# node.net
KiCad netlist of a schematic drawn in EAGLE
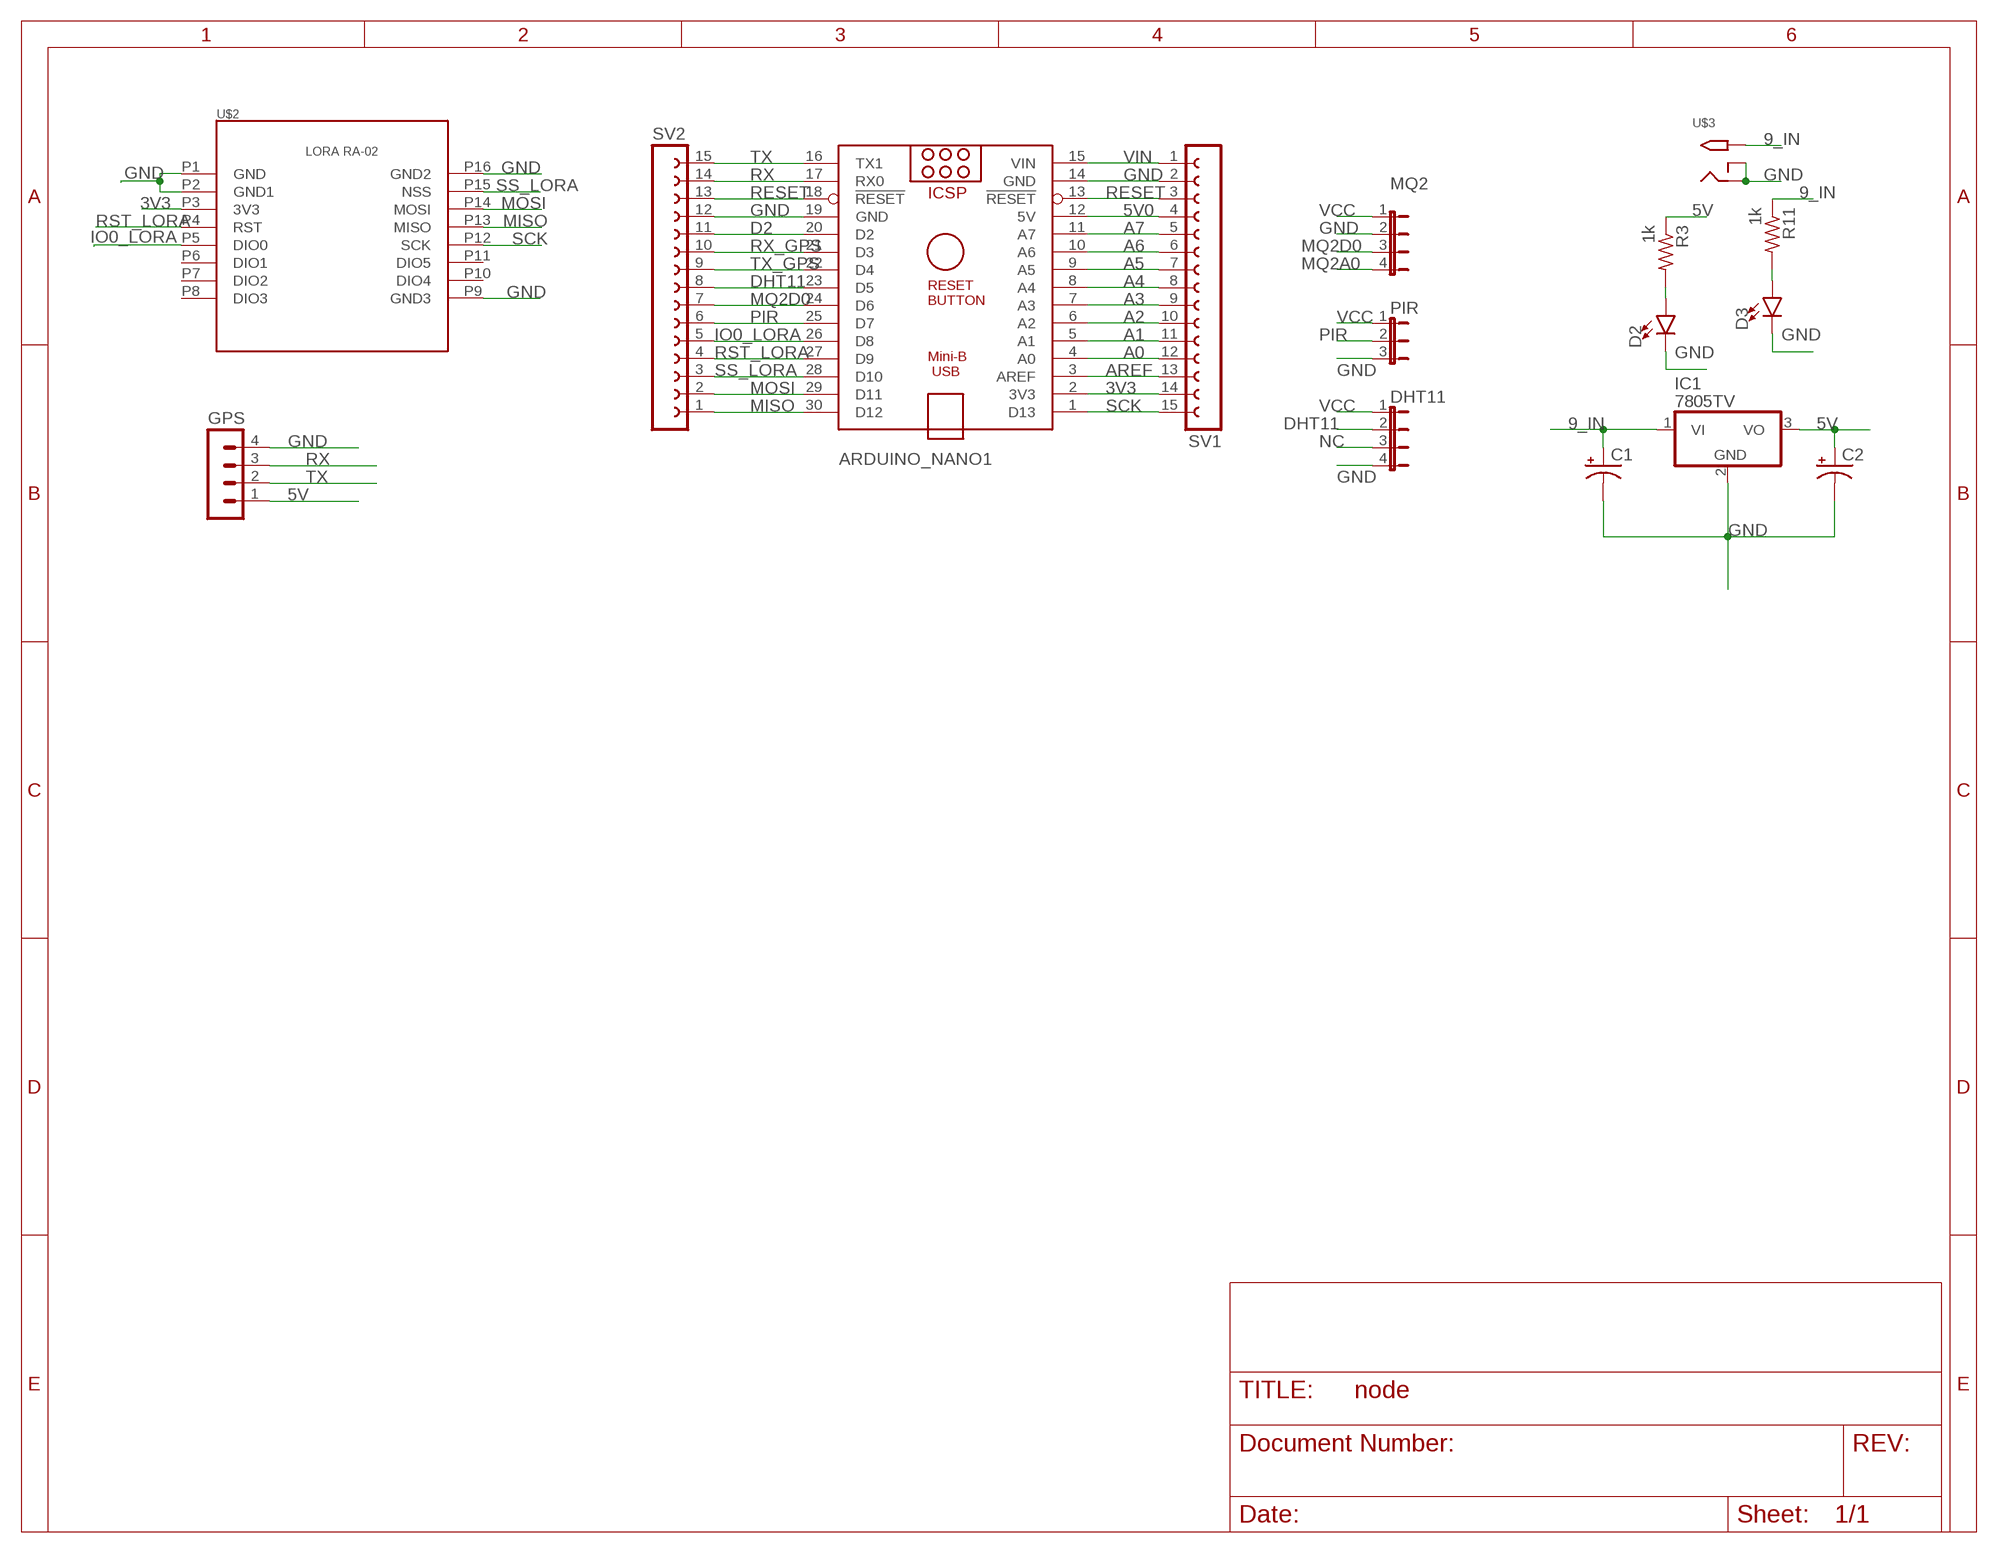
[diagram p0: schematic, sheet 1]

(export (version "E")
  (design (tool "Eeschema 10.0.6"))
  (components
    (comp (ref "ARDUINO_NANO1")
      (value "ARDUINO_NANO")
      (footprint "eagle-import:ARDUINO_NANO")
      (libsource (lib "eagle-import") (part "ARDUINO_NANO"))
    )
    (comp (ref "C1")
      (value "CPOL-USE3.5-8")
      (footprint "eagle-import:E3,5-8")
      (libsource (lib "eagle-import") (part "CPOL-USE3.5-8"))
    )
    (comp (ref "C2")
      (value "CPOL-USE3.5-8")
      (footprint "eagle-import:E3,5-8")
      (libsource (lib "eagle-import") (part "CPOL-USE3.5-8"))
    )
    (comp (ref "D2")
      (value "LED3MM")
      (footprint "eagle-import:LED_3MM")
      (libsource (lib "eagle-import") (part "LED3MM"))
    )
    (comp (ref "D3")
      (value "LED3MM")
      (footprint "eagle-import:LED_3MM")
      (libsource (lib "eagle-import") (part "LED3MM"))
    )
    (comp (ref "DHT11")
      (value "JP4E")
      (footprint "eagle-import:JP4")
      (libsource (lib "eagle-import") (part "JP4E"))
    )
    (comp (ref "GPS")
      (value "MA04-1")
      (footprint "eagle-import:MA04-1")
      (libsource (lib "eagle-import") (part "MA04-1"))
    )
    (comp (ref "IC1")
      (value "7805TV")
      (footprint "eagle-import:TO220V")
      (libsource (lib "eagle-import") (part "78TV05"))
    )
    (comp (ref "MQ2")
      (value "JP4E")
      (footprint "eagle-import:JP4")
      (libsource (lib "eagle-import") (part "JP4E"))
    )
    (comp (ref "PIR")
      (value "JP2E")
      (footprint "eagle-import:JP2")
      (libsource (lib "eagle-import") (part "JP2E"))
    )
    (comp (ref "R3")
      (value "1k")
      (footprint "eagle-import:M0805")
      (libsource (lib "eagle-import") (part "R-US_M0805"))
    )
    (comp (ref "R11")
      (value "1k")
      (footprint "eagle-import:M0805")
      (libsource (lib "eagle-import") (part "R-US_M0805"))
    )
    (comp (ref "SV1")
      (value "FE15-1")
      (footprint "eagle-import:FE15")
      (libsource (lib "eagle-import") (part "FE15-1"))
    )
    (comp (ref "SV2")
      (value "FE15-1")
      (footprint "eagle-import:FE15")
      (libsource (lib "eagle-import") (part "FE15-1"))
    )
    (comp (ref "U$2")
      (value "LORA_RA-02")
      (footprint "eagle-import:RA-02")
      (libsource (lib "eagle-import") (part "LORA_RA-02"))
    )
    (comp (ref "U$3")
      (value "2.1MMJACKTHM")
      (footprint "eagle-import:PJ-102A")
      (libsource (lib "eagle-import") (part "2.1MMJACKTHM"))
    )
  )
  (nets
    (net (code "1") (name "/3V3") (class "Default")
      (node (ref "ARDUINO_NANO1") (pin "2") (pinfunction "3V3_2") (pintype "output"))
      (node (ref "SV1") (pin "14") (pinfunction "14_14") (pintype "passive"))
      (node (ref "U$2") (pin "P3") (pinfunction "3V3_P3") (pintype "bidirectional"))
    )
    (net (code "2") (name "/5V") (class "Default")
      (node (ref "C2") (pin "+") (pinfunction "+_+") (pintype "passive"))
      (node (ref "GPS") (pin "1") (pinfunction "1_1") (pintype "passive"))
      (node (ref "IC1") (pin "3") (pinfunction "VO_3") (pintype "passive"))
      (node (ref "R3") (pin "1") (pinfunction "1_1") (pintype "passive"))
    )
    (net (code "3") (name "/5V0") (class "Default")
      (node (ref "ARDUINO_NANO1") (pin "12") (pinfunction "5V_12") (pintype "power_in"))
      (node (ref "SV1") (pin "4") (pinfunction "4_4") (pintype "passive"))
    )
    (net (code "4") (name "/9_IN") (class "Default")
      (node (ref "C1") (pin "+") (pinfunction "+_+") (pintype "passive"))
      (node (ref "IC1") (pin "1") (pinfunction "VI_1") (pintype "input"))
      (node (ref "R11") (pin "1") (pinfunction "1_1") (pintype "passive"))
      (node (ref "U$3") (pin "TIP") (pinfunction "TIP_TIP") (pintype "bidirectional"))
    )
    (net (code "5") (name "/A0") (class "Default")
      (node (ref "ARDUINO_NANO1") (pin "4") (pinfunction "A0_4") (pintype "bidirectional"))
      (node (ref "SV1") (pin "12") (pinfunction "12_12") (pintype "passive"))
    )
    (net (code "6") (name "/A1") (class "Default")
      (node (ref "ARDUINO_NANO1") (pin "5") (pinfunction "A1_5") (pintype "bidirectional"))
      (node (ref "SV1") (pin "11") (pinfunction "11_11") (pintype "passive"))
    )
    (net (code "7") (name "/A2") (class "Default")
      (node (ref "ARDUINO_NANO1") (pin "6") (pinfunction "A2_6") (pintype "bidirectional"))
      (node (ref "SV1") (pin "10") (pinfunction "10_10") (pintype "passive"))
    )
    (net (code "8") (name "/A3") (class "Default")
      (node (ref "ARDUINO_NANO1") (pin "7") (pinfunction "A3_7") (pintype "bidirectional"))
      (node (ref "SV1") (pin "9") (pinfunction "9_9") (pintype "passive"))
    )
    (net (code "9") (name "/A4") (class "Default")
      (node (ref "ARDUINO_NANO1") (pin "8") (pinfunction "A4_8") (pintype "bidirectional"))
      (node (ref "SV1") (pin "8") (pinfunction "8_8") (pintype "passive"))
    )
    (net (code "10") (name "/A5") (class "Default")
      (node (ref "ARDUINO_NANO1") (pin "9") (pinfunction "A5_9") (pintype "bidirectional"))
      (node (ref "SV1") (pin "7") (pinfunction "7_7") (pintype "passive"))
    )
    (net (code "11") (name "/A6") (class "Default")
      (node (ref "ARDUINO_NANO1") (pin "10") (pinfunction "A6_10") (pintype "bidirectional"))
      (node (ref "SV1") (pin "6") (pinfunction "6_6") (pintype "passive"))
    )
    (net (code "12") (name "/A7") (class "Default")
      (node (ref "ARDUINO_NANO1") (pin "11") (pinfunction "A7_11") (pintype "bidirectional"))
      (node (ref "SV1") (pin "5") (pinfunction "5_5") (pintype "passive"))
    )
    (net (code "13") (name "/AREF") (class "Default")
      (node (ref "ARDUINO_NANO1") (pin "3") (pinfunction "AREF_3") (pintype "input"))
      (node (ref "SV1") (pin "13") (pinfunction "13_13") (pintype "passive"))
    )
    (net (code "14") (name "/D2") (class "Default")
      (node (ref "ARDUINO_NANO1") (pin "20") (pinfunction "D2_20") (pintype "bidirectional"))
      (node (ref "SV2") (pin "11") (pinfunction "11_11") (pintype "passive"))
    )
    (net (code "15") (name "/DHT11") (class "Default")
      (node (ref "ARDUINO_NANO1") (pin "23") (pinfunction "D5_23") (pintype "bidirectional"))
      (node (ref "DHT11") (pin "2") (pinfunction "2_2") (pintype "passive"))
      (node (ref "SV2") (pin "8") (pinfunction "8_8") (pintype "passive"))
    )
    (net (code "16") (name "/GND") (class "Default")
      (node (ref "ARDUINO_NANO1") (pin "14") (pinfunction "GND_14") (pintype "power_in"))
      (node (ref "ARDUINO_NANO1") (pin "19") (pinfunction "GND_19") (pintype "power_in"))
      (node (ref "C1") (pin "-") (pinfunction "-_-") (pintype "passive"))
      (node (ref "C2") (pin "-") (pinfunction "-_-") (pintype "passive"))
      (node (ref "D2") (pin "K") (pinfunction "C_K") (pintype "passive"))
      (node (ref "D3") (pin "K") (pinfunction "C_K") (pintype "passive"))
      (node (ref "DHT11") (pin "4") (pinfunction "4_4") (pintype "passive"))
      (node (ref "GPS") (pin "4") (pinfunction "4_4") (pintype "passive"))
      (node (ref "IC1") (pin "2") (pinfunction "GND_2") (pintype "passive"))
      (node (ref "MQ2") (pin "2") (pinfunction "2_2") (pintype "passive"))
      (node (ref "PIR") (pin "3") (pinfunction "3_3") (pintype "passive"))
      (node (ref "SV1") (pin "2") (pinfunction "2_2") (pintype "passive"))
      (node (ref "SV2") (pin "12") (pinfunction "12_12") (pintype "passive"))
      (node (ref "U$2") (pin "P1") (pinfunction "GND_P1") (pintype "bidirectional"))
      (node (ref "U$2") (pin "P16") (pinfunction "GND2_P16") (pintype "bidirectional"))
      (node (ref "U$2") (pin "P2") (pinfunction "GND1_P2") (pintype "bidirectional"))
      (node (ref "U$2") (pin "P9") (pinfunction "GND3_P9") (pintype "bidirectional"))
      (node (ref "U$3") (pin "RING") (pinfunction "RING_RING") (pintype "bidirectional"))
      (node (ref "U$3") (pin "RING_SW") (pinfunction "RING_SW_RING_SW") (pintype "bidirectional"))
    )
    (net (code "17") (name "/IO0_LORA") (class "Default")
      (node (ref "ARDUINO_NANO1") (pin "26") (pinfunction "D8_26") (pintype "bidirectional"))
      (node (ref "SV2") (pin "5") (pinfunction "5_5") (pintype "passive"))
      (node (ref "U$2") (pin "P5") (pinfunction "DIO0_P5") (pintype "bidirectional"))
    )
    (net (code "18") (name "/MISO") (class "Default")
      (node (ref "ARDUINO_NANO1") (pin "30") (pinfunction "D12_30") (pintype "bidirectional"))
      (node (ref "SV2") (pin "1") (pinfunction "1_1") (pintype "passive"))
      (node (ref "U$2") (pin "P13") (pinfunction "MISO_P13") (pintype "bidirectional"))
    )
    (net (code "19") (name "/MOSI") (class "Default")
      (node (ref "ARDUINO_NANO1") (pin "29") (pinfunction "D11_29") (pintype "bidirectional"))
      (node (ref "SV2") (pin "2") (pinfunction "2_2") (pintype "passive"))
      (node (ref "U$2") (pin "P14") (pinfunction "MOSI_P14") (pintype "bidirectional"))
    )
    (net (code "20") (name "/MQ2A0") (class "Default")
      (node (ref "MQ2") (pin "4") (pinfunction "4_4") (pintype "passive"))
    )
    (net (code "21") (name "/MQ2D0") (class "Default")
      (node (ref "ARDUINO_NANO1") (pin "24") (pinfunction "D6_24") (pintype "bidirectional"))
      (node (ref "MQ2") (pin "3") (pinfunction "3_3") (pintype "passive"))
      (node (ref "SV2") (pin "7") (pinfunction "7_7") (pintype "passive"))
    )
    (net (code "22") (name "/NC") (class "Default")
      (node (ref "DHT11") (pin "3") (pinfunction "3_3") (pintype "passive"))
    )
    (net (code "23") (name "/PIR") (class "Default")
      (node (ref "ARDUINO_NANO1") (pin "25") (pinfunction "D7_25") (pintype "bidirectional"))
      (node (ref "PIR") (pin "2") (pinfunction "2_2") (pintype "passive"))
      (node (ref "SV2") (pin "6") (pinfunction "6_6") (pintype "passive"))
    )
    (net (code "24") (name "/RESET") (class "Default")
      (node (ref "ARDUINO_NANO1") (pin "13") (pinfunction "~{RESET}_13") (pintype "input"))
      (node (ref "ARDUINO_NANO1") (pin "18") (pinfunction "~{RESET}_18") (pintype "input"))
      (node (ref "SV1") (pin "3") (pinfunction "3_3") (pintype "passive"))
      (node (ref "SV2") (pin "13") (pinfunction "13_13") (pintype "passive"))
    )
    (net (code "25") (name "/RST_LORA") (class "Default")
      (node (ref "ARDUINO_NANO1") (pin "27") (pinfunction "D9_27") (pintype "bidirectional"))
      (node (ref "SV2") (pin "4") (pinfunction "4_4") (pintype "passive"))
      (node (ref "U$2") (pin "P4") (pinfunction "RST_P4") (pintype "bidirectional"))
    )
    (net (code "26") (name "/RX") (class "Default")
      (node (ref "ARDUINO_NANO1") (pin "17") (pinfunction "RX0_17") (pintype "bidirectional"))
      (node (ref "GPS") (pin "3") (pinfunction "3_3") (pintype "passive"))
      (node (ref "SV2") (pin "14") (pinfunction "14_14") (pintype "passive"))
    )
    (net (code "27") (name "/RX_GPS") (class "Default")
      (node (ref "ARDUINO_NANO1") (pin "21") (pinfunction "D3_21") (pintype "bidirectional"))
      (node (ref "SV2") (pin "10") (pinfunction "10_10") (pintype "passive"))
    )
    (net (code "28") (name "/SCK") (class "Default")
      (node (ref "ARDUINO_NANO1") (pin "1") (pinfunction "D13_1") (pintype "bidirectional"))
      (node (ref "SV1") (pin "15") (pinfunction "15_15") (pintype "passive"))
      (node (ref "U$2") (pin "P12") (pinfunction "SCK_P12") (pintype "bidirectional"))
    )
    (net (code "29") (name "/SS_LORA") (class "Default")
      (node (ref "ARDUINO_NANO1") (pin "28") (pinfunction "D10_28") (pintype "bidirectional"))
      (node (ref "SV2") (pin "3") (pinfunction "3_3") (pintype "passive"))
      (node (ref "U$2") (pin "P15") (pinfunction "NSS_P15") (pintype "bidirectional"))
    )
    (net (code "30") (name "/TX") (class "Default")
      (node (ref "ARDUINO_NANO1") (pin "16") (pinfunction "TX1_16") (pintype "bidirectional"))
      (node (ref "GPS") (pin "2") (pinfunction "2_2") (pintype "passive"))
      (node (ref "SV2") (pin "15") (pinfunction "15_15") (pintype "passive"))
    )
    (net (code "31") (name "/TX_GPS") (class "Default")
      (node (ref "ARDUINO_NANO1") (pin "22") (pinfunction "D4_22") (pintype "bidirectional"))
      (node (ref "SV2") (pin "9") (pinfunction "9_9") (pintype "passive"))
    )
    (net (code "32") (name "/VCC") (class "Default")
      (node (ref "DHT11") (pin "1") (pinfunction "1_1") (pintype "passive"))
      (node (ref "MQ2") (pin "1") (pinfunction "1_1") (pintype "passive"))
      (node (ref "PIR") (pin "1") (pinfunction "1_1") (pintype "passive"))
    )
    (net (code "33") (name "/VIN") (class "Default")
      (node (ref "ARDUINO_NANO1") (pin "15") (pinfunction "VIN_15") (pintype "power_in"))
      (node (ref "SV1") (pin "1") (pinfunction "1_1") (pintype "passive"))
    )
    (net (code "34") (name "Net-(D2-PadA)") (class "Default")
      (node (ref "D2") (pin "A") (pinfunction "A_A") (pintype "passive"))
      (node (ref "R3") (pin "2") (pinfunction "2_2") (pintype "passive"))
    )
    (net (code "35") (name "Net-(D3-PadA)") (class "Default")
      (node (ref "D3") (pin "A") (pinfunction "A_A") (pintype "passive"))
      (node (ref "R11") (pin "2") (pinfunction "2_2") (pintype "passive"))
    )
    (net (code "36") (name "unconnected-(U$2-DIO1-PadP6)") (class "Default")
      (node (ref "U$2") (pin "P6") (pinfunction "DIO1_P6") (pintype "bidirectional"))
    )
    (net (code "37") (name "unconnected-(U$2-DIO2-PadP7)") (class "Default")
      (node (ref "U$2") (pin "P7") (pinfunction "DIO2_P7") (pintype "bidirectional"))
    )
    (net (code "38") (name "unconnected-(U$2-DIO3-PadP8)") (class "Default")
      (node (ref "U$2") (pin "P8") (pinfunction "DIO3_P8") (pintype "bidirectional"))
    )
    (net (code "39") (name "unconnected-(U$2-DIO4-PadP10)") (class "Default")
      (node (ref "U$2") (pin "P10") (pinfunction "DIO4_P10") (pintype "bidirectional"))
    )
    (net (code "40") (name "unconnected-(U$2-DIO5-PadP11)") (class "Default")
      (node (ref "U$2") (pin "P11") (pinfunction "DIO5_P11") (pintype "bidirectional"))
    )
  )
)
